# m1284p-40p-breakout_board.net
KiCad netlist of a schematic drawn in EAGLE
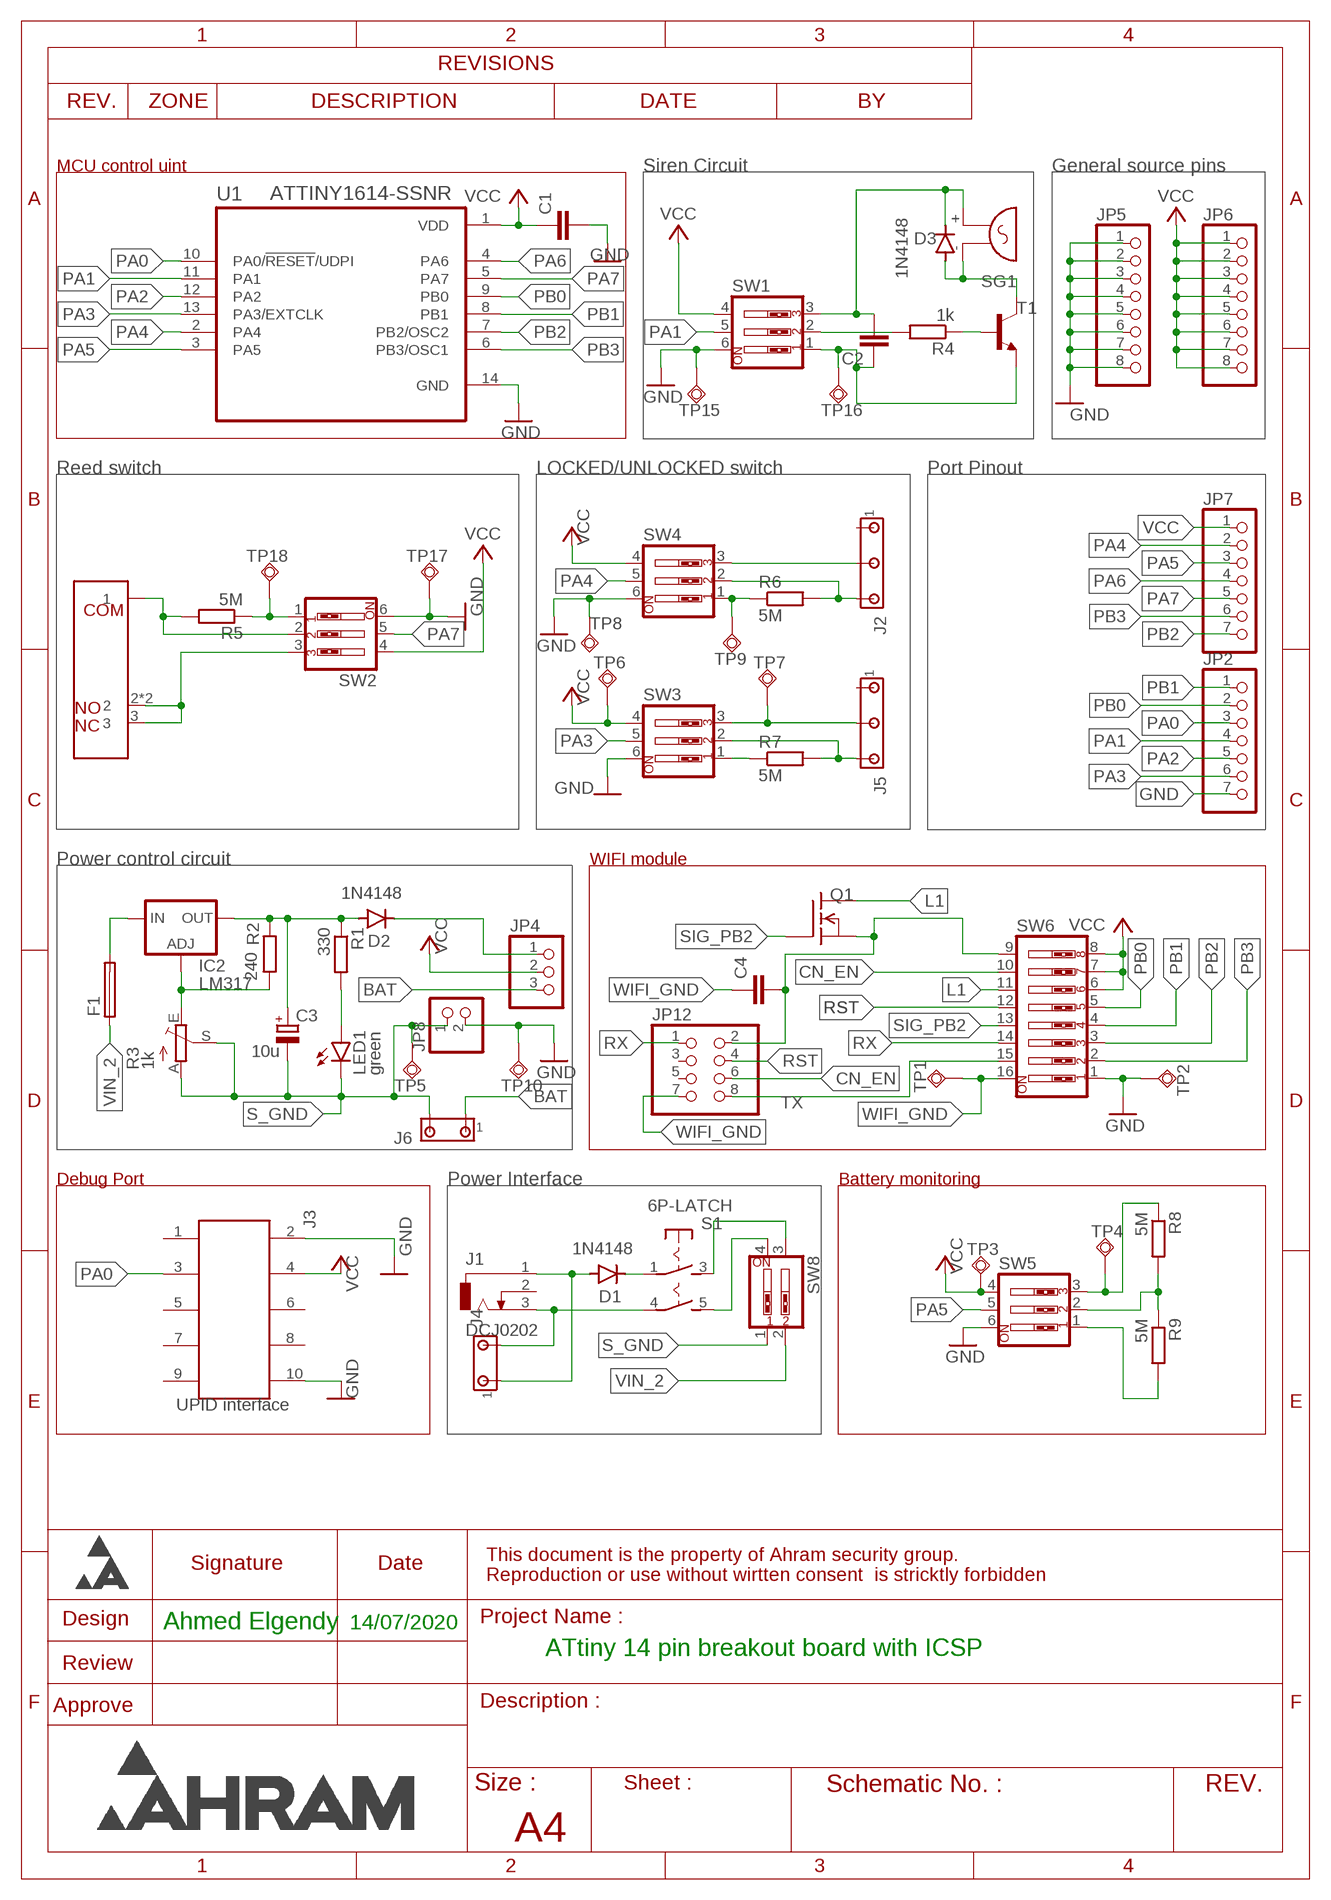
[diagram p0: schematic, sheet 1]

(export (version "E")
  (design (tool "Eeschema 10.0.6"))
  (components
    (comp (ref "C1")
      (value "C-EU025-030X050")
      (footprint "eagle-import:C025-030X050")
      (libsource (lib "eagle-import") (part "C-EU025-030X050"))
    )
    (comp (ref "C2")
      (value "C-EU025-030X050")
      (footprint "eagle-import:C025-030X050")
      (libsource (lib "eagle-import") (part "C-EU025-030X050"))
    )
    (comp (ref "C3")
      (value "10u")
      (footprint "eagle-import:E2-4")
      (libsource (lib "eagle-import") (part "CPOL-EUE2-4"))
    )
    (comp (ref "C4")
      (value "C-EU025-030X050")
      (footprint "eagle-import:C025-030X050")
      (libsource (lib "eagle-import") (part "C-EU025-030X050"))
    )
    (comp (ref "D1")
      (value "1N4148")
      (footprint "eagle-import:DO35-7")
      (libsource (lib "eagle-import") (part "1N4148DO35-7"))
    )
    (comp (ref "D2")
      (value "1N4148")
      (footprint "eagle-import:DO35-7")
      (libsource (lib "eagle-import") (part "1N4148DO35-7"))
    )
    (comp (ref "D3")
      (value "1N4148")
      (footprint "eagle-import:DO35-7")
      (libsource (lib "eagle-import") (part "1N4148DO35-7"))
    )
    (comp (ref "F1")
      (value "SH22,5A")
      (footprint "eagle-import:SH22,5A")
      (fields (field (name "MPN") "0031.7701.11"))
      (libsource (lib "eagle-import") (part "SH22,5A"))
    )
    (comp (ref "IC2")
      (value "LM317")
      (footprint "eagle-import:317TS")
      (libsource (lib "eagle-import") (part "LM317TS"))
    )
    (comp (ref "J1")
      (value "DCJ0202")
      (footprint "eagle-import:DCJ0202")
      (libsource (lib "eagle-import") (part "DCJ0202"))
    )
    (comp (ref "J2")
      (value "MTA05-156_MYVSPACE1")
      (footprint "eagle-import:10X05MTA_MYV")
      (libsource (lib "eagle-import") (part "MTA05-156_MYVSPACE1"))
    )
    (comp (ref "J3")
      (value "UPID interface")
      (footprint "eagle-import:612010235121")
      (libsource (lib "eagle-import") (part "612010235121"))
    )
    (comp (ref "J4")
      (value "MTA03-100_MYV")
      (footprint "eagle-import:10X03MTA_MYV")
      (libsource (lib "eagle-import") (part "MTA03-100_MYV"))
    )
    (comp (ref "J5")
      (value "MTA05-156_MYVSPACE1")
      (footprint "eagle-import:10X05MTA_MYV")
      (libsource (lib "eagle-import") (part "MTA05-156_MYVSPACE1"))
    )
    (comp (ref "J6")
      (value "MTA03-100_MYV")
      (footprint "eagle-import:10X03MTA_MYV")
      (libsource (lib "eagle-import") (part "MTA03-100_MYV"))
    )
    (comp (ref "JP2")
      (value "PINHD-1X7")
      (footprint "eagle-import:1X07")
      (libsource (lib "eagle-import") (part "PINHD-1X7"))
    )
    (comp (ref "JP4")
      (value "PINHD-1X3")
      (footprint "eagle-import:1X03")
      (libsource (lib "eagle-import") (part "PINHD-1X3"))
    )
    (comp (ref "JP5")
      (value "PINHD-1X8")
      (footprint "eagle-import:1X08")
      (libsource (lib "eagle-import") (part "PINHD-1X8"))
    )
    (comp (ref "JP6")
      (value "PINHD-1X8")
      (footprint "eagle-import:1X08")
      (libsource (lib "eagle-import") (part "PINHD-1X8"))
    )
    (comp (ref "JP7")
      (value "PINHD-1X7")
      (footprint "eagle-import:1X07")
      (libsource (lib "eagle-import") (part "PINHD-1X7"))
    )
    (comp (ref "JP8")
      (value "PINHD-1X2")
      (footprint "eagle-import:1X02")
      (libsource (lib "eagle-import") (part "PINHD-1X2"))
    )
    (comp (ref "JP12")
      (value "PINHD-2X4")
      (footprint "eagle-import:2X04")
      (libsource (lib "eagle-import") (part "PINHD-2X4"))
    )
    (comp (ref "LED1")
      (value "green")
      (footprint "eagle-import:LED3MM")
      (libsource (lib "eagle-import") (part "LED3MM"))
    )
    (comp (ref "Q1")
      (value "BSS295")
      (footprint "eagle-import:TO92")
      (libsource (lib "eagle-import") (part "BSS295"))
    )
    (comp (ref "R1")
      (value "330")
      (footprint "eagle-import:0204_7")
      (libsource (lib "eagle-import") (part "R-EU_0204/7"))
    )
    (comp (ref "R2")
      (value "240")
      (footprint "eagle-import:0204_7")
      (libsource (lib "eagle-import") (part "R-EU_0204/7"))
    )
    (comp (ref "R3")
      (value "1k")
      (footprint "eagle-import:RJ9W")
      (libsource (lib "eagle-import") (part "TRIM_EU-RJ9W"))
    )
    (comp (ref "R4")
      (value "1k")
      (footprint "eagle-import:0204_7")
      (libsource (lib "eagle-import") (part "R-EU_0204/7"))
    )
    (comp (ref "R5")
      (value "5M")
      (footprint "eagle-import:0204_7")
      (libsource (lib "eagle-import") (part "R-EU_0204/7"))
    )
    (comp (ref "R6")
      (value "5M")
      (footprint "eagle-import:0204_7")
      (libsource (lib "eagle-import") (part "R-EU_0204/7"))
    )
    (comp (ref "R7")
      (value "5M")
      (footprint "eagle-import:0204_7")
      (libsource (lib "eagle-import") (part "R-EU_0204/7"))
    )
    (comp (ref "R8")
      (value "5M")
      (footprint "eagle-import:0204_7")
      (libsource (lib "eagle-import") (part "R-EU_0204/7"))
    )
    (comp (ref "R9")
      (value "5M")
      (footprint "eagle-import:0204_7")
      (libsource (lib "eagle-import") (part "R-EU_0204/7"))
    )
    (comp (ref "S1")
      (value "6P-LATCH")
      (footprint "eagle-import:TACT-6P-LATCH")
      (libsource (lib "eagle-import") (part "6P-LATCH"))
    )
    (comp (ref "S2")
      (value "REED_1513")
      (footprint "eagle-import:REED_MYV")
      (libsource (lib "eagle-import") (part "REED_1513"))
    )
    (comp (ref "SG1")
      (value "F/QMX")
      (footprint "eagle-import:F_QMX")
      (libsource (lib "eagle-import") (part "F/QMX"))
    )
    (comp (ref "SW1")
      (value "SW_DIP-3")
      (footprint "eagle-import:EDG-03")
      (libsource (lib "eagle-import") (part "SW_DIP-3"))
    )
    (comp (ref "SW2")
      (value "SW_DIP-3")
      (footprint "eagle-import:EDG-03")
      (libsource (lib "eagle-import") (part "SW_DIP-3"))
    )
    (comp (ref "SW3")
      (value "SW_DIP-3")
      (footprint "eagle-import:EDG-03")
      (libsource (lib "eagle-import") (part "SW_DIP-3"))
    )
    (comp (ref "SW4")
      (value "SW_DIP-3")
      (footprint "eagle-import:EDG-03")
      (libsource (lib "eagle-import") (part "SW_DIP-3"))
    )
    (comp (ref "SW5")
      (value "SW_DIP-3")
      (footprint "eagle-import:EDG-03")
      (libsource (lib "eagle-import") (part "SW_DIP-3"))
    )
    (comp (ref "SW6")
      (value "SW_DIP-8")
      (footprint "eagle-import:EDG-08")
      (libsource (lib "eagle-import") (part "SW_DIP-8"))
    )
    (comp (ref "SW8")
      (value "SW_DIP-2")
      (footprint "eagle-import:EDG-02")
      (libsource (lib "eagle-import") (part "SW_DIP-2"))
    )
    (comp (ref "T1")
      (value "2N2222")
      (footprint "eagle-import:TO18")
      (libsource (lib "eagle-import") (part "2N2222"))
    )
    (comp (ref "TP1")
      (value "TPSQPAD1-13")
      (footprint "eagle-import:P1-13")
      (libsource (lib "eagle-import") (part "TPSQPAD1-13"))
    )
    (comp (ref "TP2")
      (value "TPSQPAD1-13")
      (footprint "eagle-import:P1-13")
      (libsource (lib "eagle-import") (part "TPSQPAD1-13"))
    )
    (comp (ref "TP3")
      (value "TPSQPAD1-13")
      (footprint "eagle-import:P1-13")
      (libsource (lib "eagle-import") (part "TPSQPAD1-13"))
    )
    (comp (ref "TP4")
      (value "TPSQPAD1-13")
      (footprint "eagle-import:P1-13")
      (libsource (lib "eagle-import") (part "TPSQPAD1-13"))
    )
    (comp (ref "TP5")
      (value "TPSQPAD1-13")
      (footprint "eagle-import:P1-13")
      (libsource (lib "eagle-import") (part "TPSQPAD1-13"))
    )
    (comp (ref "TP6")
      (value "TPSQPAD1-13")
      (footprint "eagle-import:P1-13")
      (libsource (lib "eagle-import") (part "TPSQPAD1-13"))
    )
    (comp (ref "TP7")
      (value "TPSQPAD1-13")
      (footprint "eagle-import:P1-13")
      (libsource (lib "eagle-import") (part "TPSQPAD1-13"))
    )
    (comp (ref "TP8")
      (value "TPSQPAD1-13")
      (footprint "eagle-import:P1-13")
      (libsource (lib "eagle-import") (part "TPSQPAD1-13"))
    )
    (comp (ref "TP9")
      (value "TPSQPAD1-13")
      (footprint "eagle-import:P1-13")
      (libsource (lib "eagle-import") (part "TPSQPAD1-13"))
    )
    (comp (ref "TP10")
      (value "TPSQPAD1-13")
      (footprint "eagle-import:P1-13")
      (libsource (lib "eagle-import") (part "TPSQPAD1-13"))
    )
    (comp (ref "TP15")
      (value "TPSQPAD1-13")
      (footprint "eagle-import:P1-13")
      (libsource (lib "eagle-import") (part "TPSQPAD1-13"))
    )
    (comp (ref "TP16")
      (value "TPSQPAD1-13")
      (footprint "eagle-import:P1-13")
      (libsource (lib "eagle-import") (part "TPSQPAD1-13"))
    )
    (comp (ref "TP17")
      (value "TPSQPAD1-13")
      (footprint "eagle-import:P1-13")
      (libsource (lib "eagle-import") (part "TPSQPAD1-13"))
    )
    (comp (ref "TP18")
      (value "TPSQPAD1-13")
      (footprint "eagle-import:P1-13")
      (libsource (lib "eagle-import") (part "TPSQPAD1-13"))
    )
    (comp (ref "U1")
      (value "ATTINY1614-SSNR")
      (footprint "eagle-import:SOIC127P600X175-14N")
      (fields (field (name "MF") "Microchip Technology"))
      (libsource (lib "eagle-import") (part "ATTINY1614-SSNR"))
    )
  )
  (nets
    (net (code "1") (name "/TX") (class "Default")
      (node (ref "JP12") (pin "8") (pinfunction "8_8") (pintype "passive"))
      (node (ref "SW6") (pin "15") (pinfunction "15_15") (pintype "passive"))
    )
    (net (code "2") (name "BAT") (class "Default")
      (node (ref "J6") (pin "1") (pinfunction "1_1") (pintype "passive"))
      (node (ref "JP4") (pin "3") (pinfunction "3_3") (pintype "passive"))
    )
    (net (code "3") (name "CN_EN") (class "Default")
      (node (ref "JP12") (pin "6") (pinfunction "6_6") (pintype "passive"))
      (node (ref "SW6") (pin "10") (pinfunction "10_10") (pintype "passive"))
    )
    (net (code "4") (name "GND") (class "Default")
      (node (ref "C1") (pin "2") (pinfunction "2_2") (pintype "passive"))
      (node (ref "J3") (pin "10") (pinfunction "10_10") (pintype "passive"))
      (node (ref "J3") (pin "2") (pinfunction "2_2") (pintype "passive"))
      (node (ref "JP2") (pin "7") (pinfunction "7_7") (pintype "passive"))
      (node (ref "JP5") (pin "1") (pinfunction "1_1") (pintype "passive"))
      (node (ref "JP5") (pin "2") (pinfunction "2_2") (pintype "passive"))
      (node (ref "JP5") (pin "3") (pinfunction "3_3") (pintype "passive"))
      (node (ref "JP5") (pin "4") (pinfunction "4_4") (pintype "passive"))
      (node (ref "JP5") (pin "5") (pinfunction "5_5") (pintype "passive"))
      (node (ref "JP5") (pin "6") (pinfunction "6_6") (pintype "passive"))
      (node (ref "JP5") (pin "7") (pinfunction "7_7") (pintype "passive"))
      (node (ref "JP5") (pin "8") (pinfunction "8_8") (pintype "passive"))
      (node (ref "JP8") (pin "2") (pinfunction "2_2") (pintype "passive"))
      (node (ref "SW1") (pin "6") (pinfunction "6_6") (pintype "passive"))
      (node (ref "SW2") (pin "6") (pinfunction "6_6") (pintype "passive"))
      (node (ref "SW3") (pin "6") (pinfunction "6_6") (pintype "passive"))
      (node (ref "SW4") (pin "6") (pinfunction "6_6") (pintype "passive"))
      (node (ref "SW5") (pin "6") (pinfunction "6_6") (pintype "passive"))
      (node (ref "SW6") (pin "1") (pinfunction "1_1") (pintype "passive"))
      (node (ref "TP10") (pin "TP") (pinfunction "TP_TP") (pintype "input"))
      (node (ref "TP15") (pin "TP") (pinfunction "TP_TP") (pintype "input"))
      (node (ref "TP17") (pin "TP") (pinfunction "TP_TP") (pintype "input"))
      (node (ref "TP2") (pin "TP") (pinfunction "TP_TP") (pintype "input"))
      (node (ref "TP8") (pin "TP") (pinfunction "TP_TP") (pintype "input"))
      (node (ref "U1") (pin "14") (pinfunction "GND_14") (pintype "power_in"))
    )
    (net (code "5") (name "L1") (class "Default")
      (node (ref "Q1") (pin "3") (pinfunction "D_3") (pintype "passive"))
      (node (ref "SW6") (pin "11") (pinfunction "11_11") (pintype "passive"))
    )
    (net (code "6") (name "Net-(D1-PadA)") (class "Default")
      (node (ref "D1") (pin "A") (pinfunction "A_A") (pintype "passive"))
      (node (ref "J1") (pin "1") (pinfunction "1_1") (pintype "passive"))
      (node (ref "J4") (pin "1") (pinfunction "1_1") (pintype "passive"))
    )
    (net (code "7") (name "Net-(D1-PadC)") (class "Default")
      (node (ref "D1") (pin "C") (pinfunction "C_C") (pintype "passive"))
      (node (ref "S1") (pin "1") (pinfunction "1_1") (pintype "bidirectional"))
    )
    (net (code "8") (name "Net-(D2-PadC)") (class "Default")
      (node (ref "D2") (pin "C") (pinfunction "C_C") (pintype "passive"))
      (node (ref "JP4") (pin "1") (pinfunction "1_1") (pintype "passive"))
    )
    (net (code "9") (name "Net-(IC2-ADJ)") (class "Default")
      (node (ref "IC2") (pin "1") (pinfunction "ADJ_1") (pintype "input"))
      (node (ref "R2") (pin "1") (pinfunction "1_1") (pintype "passive"))
      (node (ref "R3") (pin "E") (pinfunction "E_E") (pintype "passive"))
    )
    (net (code "10") (name "Net-(IC2-IN)") (class "Default")
      (node (ref "F1") (pin "2") (pinfunction "2_2") (pintype "passive"))
      (node (ref "IC2") (pin "3") (pinfunction "IN_3") (pintype "input"))
    )
    (net (code "11") (name "Net-(IC2-OUT)") (class "Default")
      (node (ref "C3") (pin "+") (pinfunction "+_+") (pintype "passive"))
      (node (ref "D2") (pin "A") (pinfunction "A_A") (pintype "passive"))
      (node (ref "IC2") (pin "2") (pinfunction "OUT_2") (pintype "passive"))
      (node (ref "R1") (pin "1") (pinfunction "1_1") (pintype "passive"))
      (node (ref "R2") (pin "2") (pinfunction "2_2") (pintype "passive"))
    )
    (net (code "12") (name "Net-(J2-Pad3)") (class "Default")
      (node (ref "J2") (pin "3") (pinfunction "3_3") (pintype "passive"))
      (node (ref "SW4") (pin "3") (pinfunction "3_3") (pintype "passive"))
    )
    (net (code "13") (name "Net-(J2-Pad5)") (class "Default")
      (node (ref "J2") (pin "5") (pinfunction "5_5") (pintype "passive"))
      (node (ref "R6") (pin "2") (pinfunction "2_2") (pintype "passive"))
      (node (ref "SW4") (pin "2") (pinfunction "2_2") (pintype "passive"))
    )
    (net (code "14") (name "Net-(J5-Pad3)") (class "Default")
      (node (ref "J5") (pin "3") (pinfunction "3_3") (pintype "passive"))
      (node (ref "SW3") (pin "3") (pinfunction "3_3") (pintype "passive"))
      (node (ref "TP7") (pin "TP") (pinfunction "TP_TP") (pintype "input"))
    )
    (net (code "15") (name "Net-(J5-Pad5)") (class "Default")
      (node (ref "J5") (pin "5") (pinfunction "5_5") (pintype "passive"))
      (node (ref "R7") (pin "2") (pinfunction "2_2") (pintype "passive"))
      (node (ref "SW3") (pin "2") (pinfunction "2_2") (pintype "passive"))
    )
    (net (code "16") (name "Net-(LED1-PadA)") (class "Default")
      (node (ref "LED1") (pin "A") (pinfunction "A_A") (pintype "passive"))
      (node (ref "R1") (pin "2") (pinfunction "2_2") (pintype "passive"))
    )
    (net (code "17") (name "Net-(Q1-S)") (class "Default")
      (node (ref "C4") (pin "2") (pinfunction "2_2") (pintype "passive"))
      (node (ref "JP12") (pin "2") (pinfunction "2_2") (pintype "passive"))
      (node (ref "Q1") (pin "1") (pinfunction "S_1") (pintype "passive"))
      (node (ref "SW6") (pin "9") (pinfunction "9_9") (pintype "passive"))
    )
    (net (code "18") (name "Net-(R4-Pad2)") (class "Default")
      (node (ref "R4") (pin "2") (pinfunction "2_2") (pintype "passive"))
      (node (ref "SW1") (pin "2") (pinfunction "2_2") (pintype "passive"))
    )
    (net (code "19") (name "Net-(R5-Pad1)") (class "Default")
      (node (ref "R5") (pin "1") (pinfunction "1_1") (pintype "passive"))
      (node (ref "SW2") (pin "1") (pinfunction "1_1") (pintype "passive"))
      (node (ref "TP18") (pin "TP") (pinfunction "TP_TP") (pintype "input"))
    )
    (net (code "20") (name "Net-(R5-Pad2)") (class "Default")
      (node (ref "R5") (pin "2") (pinfunction "2_2") (pintype "passive"))
      (node (ref "S2") (pin "1") (pinfunction "1_1") (pintype "bidirectional"))
      (node (ref "SW2") (pin "2") (pinfunction "2_2") (pintype "passive"))
    )
    (net (code "21") (name "Net-(R6-Pad1)") (class "Default")
      (node (ref "R6") (pin "1") (pinfunction "1_1") (pintype "passive"))
      (node (ref "SW4") (pin "1") (pinfunction "1_1") (pintype "passive"))
      (node (ref "TP9") (pin "TP") (pinfunction "TP_TP") (pintype "input"))
    )
    (net (code "22") (name "Net-(R7-Pad1)") (class "Default")
      (node (ref "R7") (pin "1") (pinfunction "1_1") (pintype "passive"))
      (node (ref "SW3") (pin "1") (pinfunction "1_1") (pintype "passive"))
    )
    (net (code "23") (name "Net-(R8-Pad1)") (class "Default")
      (node (ref "R8") (pin "1") (pinfunction "1_1") (pintype "passive"))
      (node (ref "SW5") (pin "3") (pinfunction "3_3") (pintype "passive"))
      (node (ref "TP4") (pin "TP") (pinfunction "TP_TP") (pintype "input"))
    )
    (net (code "24") (name "Net-(R8-Pad2)") (class "Default")
      (node (ref "R8") (pin "2") (pinfunction "2_2") (pintype "passive"))
      (node (ref "R9") (pin "1") (pinfunction "1_1") (pintype "passive"))
      (node (ref "SW5") (pin "2") (pinfunction "2_2") (pintype "passive"))
    )
    (net (code "25") (name "Net-(R9-Pad2)") (class "Default")
      (node (ref "R9") (pin "2") (pinfunction "2_2") (pintype "passive"))
      (node (ref "SW5") (pin "1") (pinfunction "1_1") (pintype "passive"))
    )
    (net (code "26") (name "Net-(S1-2)") (class "Default")
      (node (ref "S1") (pin "3") (pinfunction "2_3") (pintype "bidirectional"))
      (node (ref "SW8") (pin "3") (pinfunction "3_3") (pintype "passive"))
    )
    (net (code "27") (name "Net-(S1-3)") (class "Default")
      (node (ref "J1") (pin "3") (pinfunction "3_3") (pintype "passive"))
      (node (ref "J4") (pin "3") (pinfunction "3_3") (pintype "passive"))
      (node (ref "S1") (pin "4") (pinfunction "3_4") (pintype "bidirectional"))
    )
    (net (code "28") (name "Net-(S1-4)") (class "Default")
      (node (ref "S1") (pin "5") (pinfunction "4_5") (pintype "bidirectional"))
      (node (ref "SW8") (pin "4") (pinfunction "4_4") (pintype "passive"))
    )
    (net (code "29") (name "Net-(S2-2-Pad4)") (class "Default")
      (node (ref "S2") (pin "2") (pinfunction "2_2") (pintype "bidirectional"))
      (node (ref "S2") (pin "3") (pinfunction "3_3") (pintype "bidirectional"))
      (node (ref "S2") (pin "4") (pinfunction "2_4") (pintype "bidirectional"))
      (node (ref "SW2") (pin "3") (pinfunction "3_3") (pintype "passive"))
    )
    (net (code "30") (name "Net-(SG1-1)") (class "Default")
      (node (ref "D3") (pin "A") (pinfunction "A_A") (pintype "passive"))
      (node (ref "SG1") (pin "-") (pinfunction "1_-") (pintype "passive"))
      (node (ref "T1") (pin "3") (pinfunction "C_3") (pintype "passive"))
    )
    (net (code "31") (name "Net-(SG1-2)") (class "Default")
      (node (ref "C2") (pin "2") (pinfunction "2_2") (pintype "passive"))
      (node (ref "D3") (pin "C") (pinfunction "C_C") (pintype "passive"))
      (node (ref "SG1") (pin "+") (pinfunction "2_+") (pintype "passive"))
      (node (ref "SW1") (pin "3") (pinfunction "3_3") (pintype "passive"))
    )
    (net (code "32") (name "Net-(T1-B)") (class "Default")
      (node (ref "R4") (pin "1") (pinfunction "1_1") (pintype "passive"))
      (node (ref "T1") (pin "2") (pinfunction "B_2") (pintype "passive"))
    )
    (net (code "33") (name "Net-(T1-E)") (class "Default")
      (node (ref "C2") (pin "1") (pinfunction "1_1") (pintype "passive"))
      (node (ref "SW1") (pin "1") (pinfunction "1_1") (pintype "passive"))
      (node (ref "T1") (pin "1") (pinfunction "E_1") (pintype "passive"))
      (node (ref "TP16") (pin "TP") (pinfunction "TP_TP") (pintype "input"))
    )
    (net (code "34") (name "PA0") (class "Default")
      (node (ref "J3") (pin "3") (pinfunction "3_3") (pintype "passive"))
      (node (ref "JP2") (pin "3") (pinfunction "3_3") (pintype "passive"))
      (node (ref "U1") (pin "10") (pinfunction "PA0/~{RESET}/UDPI_10") (pintype "bidirectional"))
    )
    (net (code "35") (name "PA1") (class "Default")
      (node (ref "JP2") (pin "4") (pinfunction "4_4") (pintype "passive"))
      (node (ref "SW1") (pin "5") (pinfunction "5_5") (pintype "passive"))
      (node (ref "U1") (pin "11") (pinfunction "PA1_11") (pintype "bidirectional"))
    )
    (net (code "36") (name "PA2") (class "Default")
      (node (ref "JP2") (pin "5") (pinfunction "5_5") (pintype "passive"))
      (node (ref "U1") (pin "12") (pinfunction "PA2_12") (pintype "bidirectional"))
    )
    (net (code "37") (name "PA3") (class "Default")
      (node (ref "JP2") (pin "6") (pinfunction "6_6") (pintype "passive"))
      (node (ref "SW3") (pin "5") (pinfunction "5_5") (pintype "passive"))
      (node (ref "U1") (pin "13") (pinfunction "PA3/EXTCLK_13") (pintype "bidirectional"))
    )
    (net (code "38") (name "PA4") (class "Default")
      (node (ref "JP7") (pin "2") (pinfunction "2_2") (pintype "passive"))
      (node (ref "SW4") (pin "5") (pinfunction "5_5") (pintype "passive"))
      (node (ref "U1") (pin "2") (pinfunction "PA4_2") (pintype "bidirectional"))
    )
    (net (code "39") (name "PA5") (class "Default")
      (node (ref "JP7") (pin "3") (pinfunction "3_3") (pintype "passive"))
      (node (ref "SW5") (pin "5") (pinfunction "5_5") (pintype "passive"))
      (node (ref "U1") (pin "3") (pinfunction "PA5_3") (pintype "bidirectional"))
    )
    (net (code "40") (name "PA6") (class "Default")
      (node (ref "JP7") (pin "4") (pinfunction "4_4") (pintype "passive"))
      (node (ref "U1") (pin "4") (pinfunction "PA6_4") (pintype "bidirectional"))
    )
    (net (code "41") (name "PA7") (class "Default")
      (node (ref "JP7") (pin "5") (pinfunction "5_5") (pintype "passive"))
      (node (ref "SW2") (pin "5") (pinfunction "5_5") (pintype "passive"))
      (node (ref "U1") (pin "5") (pinfunction "PA7_5") (pintype "bidirectional"))
    )
    (net (code "42") (name "PB0") (class "Default")
      (node (ref "JP2") (pin "2") (pinfunction "2_2") (pintype "passive"))
      (node (ref "SW6") (pin "5") (pinfunction "5_5") (pintype "passive"))
      (node (ref "U1") (pin "9") (pinfunction "PB0_9") (pintype "bidirectional"))
    )
    (net (code "43") (name "PB1") (class "Default")
      (node (ref "JP2") (pin "1") (pinfunction "1_1") (pintype "passive"))
      (node (ref "SW6") (pin "4") (pinfunction "4_4") (pintype "passive"))
      (node (ref "U1") (pin "8") (pinfunction "PB1_8") (pintype "bidirectional"))
    )
    (net (code "44") (name "PB2") (class "Default")
      (node (ref "JP7") (pin "7") (pinfunction "7_7") (pintype "passive"))
      (node (ref "SW6") (pin "3") (pinfunction "3_3") (pintype "passive"))
      (node (ref "U1") (pin "7") (pinfunction "PB2/OSC2_7") (pintype "bidirectional"))
    )
    (net (code "45") (name "PB3") (class "Default")
      (node (ref "JP7") (pin "6") (pinfunction "6_6") (pintype "passive"))
      (node (ref "SW6") (pin "2") (pinfunction "2_2") (pintype "passive"))
      (node (ref "U1") (pin "6") (pinfunction "PB3/OSC1_6") (pintype "bidirectional"))
    )
    (net (code "46") (name "RST") (class "Default")
      (node (ref "JP12") (pin "4") (pinfunction "4_4") (pintype "passive"))
      (node (ref "SW6") (pin "12") (pinfunction "12_12") (pintype "passive"))
    )
    (net (code "47") (name "RX") (class "Default")
      (node (ref "JP12") (pin "1") (pinfunction "1_1") (pintype "passive"))
      (node (ref "SW6") (pin "14") (pinfunction "14_14") (pintype "passive"))
    )
    (net (code "48") (name "SIG_PB2") (class "Default")
      (node (ref "Q1") (pin "2") (pinfunction "G_2") (pintype "passive"))
      (node (ref "SW6") (pin "13") (pinfunction "13_13") (pintype "passive"))
    )
    (net (code "49") (name "S_GND") (class "Default")
      (node (ref "C3") (pin "-") (pinfunction "-_-") (pintype "passive"))
      (node (ref "J6") (pin "3") (pinfunction "3_3") (pintype "passive"))
      (node (ref "JP8") (pin "1") (pinfunction "1_1") (pintype "passive"))
      (node (ref "LED1") (pin "K") (pinfunction "C_K") (pintype "passive"))
      (node (ref "R3") (pin "A") (pinfunction "A_A") (pintype "passive"))
      (node (ref "R3") (pin "S") (pinfunction "S_S") (pintype "passive"))
      (node (ref "SW8") (pin "1") (pinfunction "1_1") (pintype "passive"))
      (node (ref "TP5") (pin "TP") (pinfunction "TP_TP") (pintype "input"))
    )
    (net (code "50") (name "VCC") (class "Default")
      (node (ref "C1") (pin "1") (pinfunction "1_1") (pintype "passive"))
      (node (ref "J3") (pin "4") (pinfunction "4_4") (pintype "passive"))
      (node (ref "JP4") (pin "2") (pinfunction "2_2") (pintype "passive"))
      (node (ref "JP6") (pin "1") (pinfunction "1_1") (pintype "passive"))
      (node (ref "JP6") (pin "2") (pinfunction "2_2") (pintype "passive"))
      (node (ref "JP6") (pin "3") (pinfunction "3_3") (pintype "passive"))
      (node (ref "JP6") (pin "4") (pinfunction "4_4") (pintype "passive"))
      (node (ref "JP6") (pin "5") (pinfunction "5_5") (pintype "passive"))
      (node (ref "JP6") (pin "6") (pinfunction "6_6") (pintype "passive"))
      (node (ref "JP6") (pin "7") (pinfunction "7_7") (pintype "passive"))
      (node (ref "JP6") (pin "8") (pinfunction "8_8") (pintype "passive"))
      (node (ref "JP7") (pin "1") (pinfunction "1_1") (pintype "passive"))
      (node (ref "SW1") (pin "4") (pinfunction "4_4") (pintype "passive"))
      (node (ref "SW2") (pin "4") (pinfunction "4_4") (pintype "passive"))
      (node (ref "SW3") (pin "4") (pinfunction "4_4") (pintype "passive"))
      (node (ref "SW4") (pin "4") (pinfunction "4_4") (pintype "passive"))
      (node (ref "SW5") (pin "4") (pinfunction "4_4") (pintype "passive"))
      (node (ref "SW6") (pin "6") (pinfunction "6_6") (pintype "passive"))
      (node (ref "SW6") (pin "7") (pinfunction "7_7") (pintype "passive"))
      (node (ref "SW6") (pin "8") (pinfunction "8_8") (pintype "passive"))
      (node (ref "TP3") (pin "TP") (pinfunction "TP_TP") (pintype "input"))
      (node (ref "TP6") (pin "TP") (pinfunction "TP_TP") (pintype "input"))
      (node (ref "U1") (pin "1") (pinfunction "VDD_1") (pintype "power_in"))
    )
    (net (code "51") (name "VIN_2") (class "Default")
      (node (ref "F1") (pin "1") (pinfunction "1_1") (pintype "passive"))
      (node (ref "SW8") (pin "2") (pinfunction "2_2") (pintype "passive"))
    )
    (net (code "52") (name "WIFI_GND") (class "Default")
      (node (ref "C4") (pin "1") (pinfunction "1_1") (pintype "passive"))
      (node (ref "JP12") (pin "7") (pinfunction "7_7") (pintype "passive"))
      (node (ref "SW6") (pin "16") (pinfunction "16_16") (pintype "passive"))
      (node (ref "TP1") (pin "TP") (pinfunction "TP_TP") (pintype "input"))
    )
    (net (code "53") (name "unconnected-(J1-Pad2)") (class "Default")
      (node (ref "J1") (pin "2") (pinfunction "2_2") (pintype "passive"))
    )
    (net (code "54") (name "unconnected-(J2-Pad1)") (class "Default")
      (node (ref "J2") (pin "1") (pinfunction "1_1") (pintype "passive"))
    )
    (net (code "55") (name "unconnected-(J3-Pad1)") (class "Default")
      (node (ref "J3") (pin "1") (pinfunction "1_1") (pintype "passive"))
    )
    (net (code "56") (name "unconnected-(J3-Pad5)") (class "Default")
      (node (ref "J3") (pin "5") (pinfunction "5_5") (pintype "passive"))
    )
    (net (code "57") (name "unconnected-(J3-Pad6)") (class "Default")
      (node (ref "J3") (pin "6") (pinfunction "6_6") (pintype "passive"))
    )
    (net (code "58") (name "unconnected-(J3-Pad7)") (class "Default")
      (node (ref "J3") (pin "7") (pinfunction "7_7") (pintype "passive"))
    )
    (net (code "59") (name "unconnected-(J3-Pad8)") (class "Default")
      (node (ref "J3") (pin "8") (pinfunction "8_8") (pintype "passive"))
    )
    (net (code "60") (name "unconnected-(J3-Pad9)") (class "Default")
      (node (ref "J3") (pin "9") (pinfunction "9_9") (pintype "passive"))
    )
    (net (code "61") (name "unconnected-(J5-Pad1)") (class "Default")
      (node (ref "J5") (pin "1") (pinfunction "1_1") (pintype "passive"))
    )
    (net (code "62") (name "unconnected-(JP12-Pad3)") (class "Default")
      (node (ref "JP12") (pin "3") (pinfunction "3_3") (pintype "passive"))
    )
    (net (code "63") (name "unconnected-(JP12-Pad5)") (class "Default")
      (node (ref "JP12") (pin "5") (pinfunction "5_5") (pintype "passive"))
    )
  )
)
